# SPD.net
KiCad netlist of a schematic drawn in Altium Designer
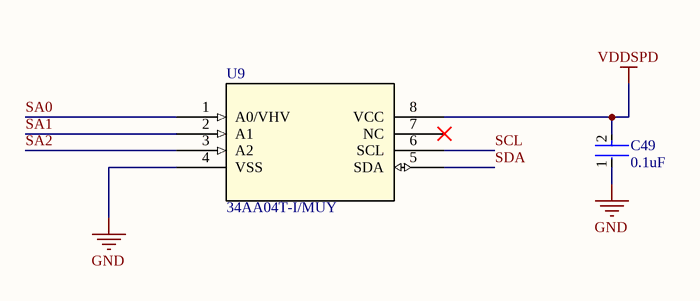
[diagram p0: SPD.SchDoc]

(export (version "E")
  (design (tool "Eeschema 10.0.6"))
  (components
    (comp (ref "C49")
      (value "0.1uF")
      (footprint "FP-GRM15-MFG")
      (description "CAP CER 0.1UF 16V X7R 0402")
      (fields (field (name "MANUFACTURER PART NUMBER") "GRM155R71C104KA88D") (field (name "TOLERANCE") "10%"))
      (libsource (lib "Altium Content Vault") (part "236180d848d6139a670b325ea6854c9"))
    )
    (comp (ref "U9")
      (value "34AA04T-I/MUY")
      (footprint "UDFN8_2x3MC_MCH")
      (description "No Description Available")
      (fields (field (name "COPYRIGHT") "Copyright (C) 2026 Ultra Librarian. All rights reserved."))
      (libsource (lib "34AA04T-IMUY") (part "34AA04T-IMUY"))
    )
  )
  (nets
    (net (code "1") (name "/SA0") (class "Default")
      (node (ref "U9") (pin "1") (pinfunction "A0/VHV_1") (pintype "input"))
    )
    (net (code "2") (name "/SA1") (class "Default")
      (node (ref "U9") (pin "2") (pinfunction "A1_2") (pintype "input"))
    )
    (net (code "3") (name "/SA2") (class "Default")
      (node (ref "U9") (pin "3") (pinfunction "A2_3") (pintype "input"))
    )
    (net (code "4") (name "/SCL") (class "Default")
      (node (ref "U9") (pin "6") (pinfunction "SCL_6") (pintype "passive"))
    )
    (net (code "5") (name "/SDA") (class "Default")
      (node (ref "U9") (pin "5") (pinfunction "SDA_5") (pintype "bidirectional"))
    )
    (net (code "6") (name "GND") (class "Default")
      (node (ref "C49") (pin "1") (pinfunction "1_1") (pintype "passive"))
      (node (ref "U9") (pin "4") (pinfunction "VSS_4") (pintype "power_in"))
    )
    (net (code "7") (name "VDDSPD") (class "Default")
      (node (ref "C49") (pin "2") (pinfunction "2_2") (pintype "passive"))
      (node (ref "U9") (pin "8") (pinfunction "VCC_8") (pintype "power_in"))
    )
    (net (code "8") (name "unconnected-(U9-NC-Pad7)") (class "Default")
      (node (ref "U9") (pin "7") (pinfunction "NC_7") (pintype "passive+no_connect"))
    )
  )
)
